# untitled.net
KiCad netlist of a schematic drawn in EAGLE
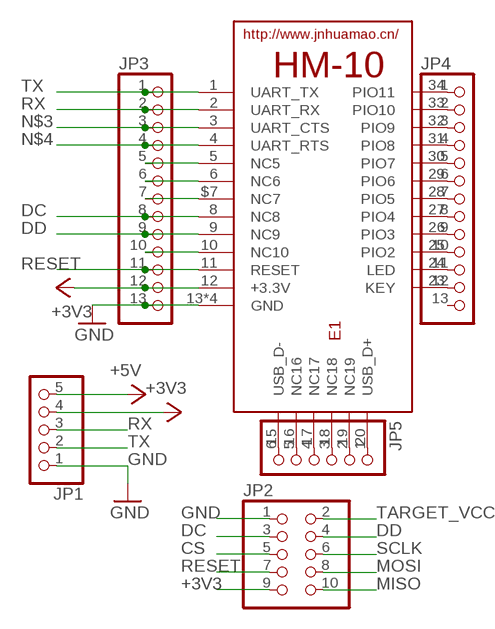
[diagram p0: schematic, sheet 1]

(export (version "E")
  (design (tool "Eeschema 10.0.6"))
  (components
    (comp (ref "E1")
      (value "HM-10-BOARD")
      (footprint "eagle-import:26.9X13X2.2_BOARD")
      (libsource (lib "eagle-import") (part "HM-10-BOARD"))
    )
    (comp (ref "JP1")
      (value "PINHD-1X5")
      (footprint "eagle-import:1X05")
      (libsource (lib "eagle-import") (part "PINHD-1X5"))
    )
    (comp (ref "JP2")
      (value "PINHD-2X5")
      (footprint "eagle-import:2X05")
      (libsource (lib "eagle-import") (part "PINHD-2X5"))
    )
    (comp (ref "JP3")
      (value "PINHD-1X13")
      (footprint "eagle-import:1X13")
      (libsource (lib "eagle-import") (part "PINHD-1X13"))
    )
    (comp (ref "JP4")
      (value "PINHD-1X13")
      (footprint "eagle-import:1X13")
      (libsource (lib "eagle-import") (part "PINHD-1X13"))
    )
    (comp (ref "JP5")
      (value "PINHD-1X6")
      (footprint "eagle-import:1X06")
      (libsource (lib "eagle-import") (part "PINHD-1X6"))
    )
  )
  (nets
    (net (code "1") (name "+3V3") (class "Default")
      (node (ref "E1") (pin "12") (pinfunction "+3.3V_12") (pintype "bidirectional"))
      (node (ref "JP1") (pin "4") (pinfunction "4_4") (pintype "passive"))
      (node (ref "JP2") (pin "9") (pinfunction "9_9") (pintype "passive"))
      (node (ref "JP3") (pin "12") (pinfunction "12_12") (pintype "passive"))
    )
    (net (code "2") (name "+5V") (class "Default")
      (node (ref "JP1") (pin "5") (pinfunction "5_5") (pintype "passive"))
    )
    (net (code "3") (name "/CS") (class "Default")
      (node (ref "JP2") (pin "5") (pinfunction "5_5") (pintype "passive"))
    )
    (net (code "4") (name "/DC") (class "Default")
      (node (ref "E1") (pin "8") (pinfunction "NC8_8") (pintype "bidirectional"))
      (node (ref "JP2") (pin "3") (pinfunction "3_3") (pintype "passive"))
      (node (ref "JP3") (pin "8") (pinfunction "8_8") (pintype "passive"))
    )
    (net (code "5") (name "/DD") (class "Default")
      (node (ref "E1") (pin "9") (pinfunction "NC9_9") (pintype "bidirectional"))
      (node (ref "JP2") (pin "4") (pinfunction "4_4") (pintype "passive"))
      (node (ref "JP3") (pin "9") (pinfunction "9_9") (pintype "passive"))
    )
    (net (code "6") (name "/MISO") (class "Default")
      (node (ref "JP2") (pin "10") (pinfunction "10_10") (pintype "passive"))
    )
    (net (code "7") (name "/MOSI") (class "Default")
      (node (ref "JP2") (pin "8") (pinfunction "8_8") (pintype "passive"))
    )
    (net (code "8") (name "/N$3") (class "Default")
      (node (ref "E1") (pin "3") (pinfunction "UART_CTS_3") (pintype "bidirectional"))
      (node (ref "JP3") (pin "3") (pinfunction "3_3") (pintype "passive"))
    )
    (net (code "9") (name "/N$4") (class "Default")
      (node (ref "E1") (pin "4") (pinfunction "UART_RTS_4") (pintype "bidirectional"))
      (node (ref "JP3") (pin "4") (pinfunction "4_4") (pintype "passive"))
    )
    (net (code "10") (name "/RESET") (class "Default")
      (node (ref "E1") (pin "11") (pinfunction "RESET_11") (pintype "bidirectional"))
      (node (ref "JP2") (pin "7") (pinfunction "7_7") (pintype "passive"))
      (node (ref "JP3") (pin "11") (pinfunction "11_11") (pintype "passive"))
    )
    (net (code "11") (name "/RX") (class "Default")
      (node (ref "E1") (pin "2") (pinfunction "UART_RX_2") (pintype "bidirectional"))
      (node (ref "JP1") (pin "3") (pinfunction "3_3") (pintype "passive"))
      (node (ref "JP3") (pin "2") (pinfunction "2_2") (pintype "passive"))
    )
    (net (code "12") (name "/SCLK") (class "Default")
      (node (ref "JP2") (pin "6") (pinfunction "6_6") (pintype "passive"))
    )
    (net (code "13") (name "/TARGET_VCC") (class "Default")
      (node (ref "JP2") (pin "2") (pinfunction "2_2") (pintype "passive"))
    )
    (net (code "14") (name "/TX") (class "Default")
      (node (ref "E1") (pin "1") (pinfunction "UART_TX_1") (pintype "bidirectional"))
      (node (ref "JP1") (pin "2") (pinfunction "2_2") (pintype "passive"))
      (node (ref "JP3") (pin "1") (pinfunction "1_1") (pintype "passive"))
    )
    (net (code "15") (name "GND") (class "Default")
      (node (ref "E1") (pin "13") (pinfunction "GND_13") (pintype "bidirectional"))
      (node (ref "E1") (pin "14") (pinfunction "GND_14") (pintype "bidirectional"))
      (node (ref "E1") (pin "21") (pinfunction "GND_21") (pintype "bidirectional"))
      (node (ref "E1") (pin "22") (pinfunction "GND_22") (pintype "bidirectional"))
      (node (ref "JP1") (pin "1") (pinfunction "1_1") (pintype "passive"))
      (node (ref "JP2") (pin "1") (pinfunction "1_1") (pintype "passive"))
      (node (ref "JP3") (pin "13") (pinfunction "13_13") (pintype "passive"))
    )
    (net (code "16") (name "Net-(E1-KEY)") (class "Default")
      (node (ref "E1") (pin "23") (pinfunction "KEY_23") (pintype "bidirectional"))
      (node (ref "JP4") (pin "12") (pinfunction "12_12") (pintype "passive"))
    )
    (net (code "17") (name "Net-(E1-LED)") (class "Default")
      (node (ref "E1") (pin "24") (pinfunction "LED_24") (pintype "bidirectional"))
      (node (ref "JP4") (pin "11") (pinfunction "11_11") (pintype "passive"))
    )
    (net (code "18") (name "Net-(E1-NC5)") (class "Default")
      (node (ref "E1") (pin "5") (pinfunction "NC5_5") (pintype "bidirectional"))
      (node (ref "JP3") (pin "5") (pinfunction "5_5") (pintype "passive"))
    )
    (net (code "19") (name "Net-(E1-NC6)") (class "Default")
      (node (ref "E1") (pin "6") (pinfunction "NC6_6") (pintype "bidirectional"))
      (node (ref "JP3") (pin "6") (pinfunction "6_6") (pintype "passive"))
    )
    (net (code "20") (name "Net-(E1-NC7)") (class "Default")
      (node (ref "E1") (pin "$7") (pinfunction "NC7_$7") (pintype "bidirectional"))
      (node (ref "JP3") (pin "7") (pinfunction "7_7") (pintype "passive"))
    )
    (net (code "21") (name "Net-(E1-NC10)") (class "Default")
      (node (ref "E1") (pin "10") (pinfunction "NC10_10") (pintype "bidirectional"))
      (node (ref "JP3") (pin "10") (pinfunction "10_10") (pintype "passive"))
    )
    (net (code "22") (name "Net-(E1-NC16)") (class "Default")
      (node (ref "E1") (pin "16") (pinfunction "NC16_16") (pintype "bidirectional"))
      (node (ref "JP5") (pin "5") (pinfunction "5_5") (pintype "passive"))
    )
    (net (code "23") (name "Net-(E1-NC17)") (class "Default")
      (node (ref "E1") (pin "17") (pinfunction "NC17_17") (pintype "bidirectional"))
      (node (ref "JP5") (pin "4") (pinfunction "4_4") (pintype "passive"))
    )
    (net (code "24") (name "Net-(E1-NC18)") (class "Default")
      (node (ref "E1") (pin "18") (pinfunction "NC18_18") (pintype "bidirectional"))
      (node (ref "JP5") (pin "3") (pinfunction "3_3") (pintype "passive"))
    )
    (net (code "25") (name "Net-(E1-NC19)") (class "Default")
      (node (ref "E1") (pin "19") (pinfunction "NC19_19") (pintype "bidirectional"))
      (node (ref "JP5") (pin "2") (pinfunction "2_2") (pintype "passive"))
    )
    (net (code "26") (name "Net-(E1-PIO2)") (class "Default")
      (node (ref "E1") (pin "25") (pinfunction "PIO2_25") (pintype "bidirectional"))
      (node (ref "JP4") (pin "10") (pinfunction "10_10") (pintype "passive"))
    )
    (net (code "27") (name "Net-(E1-PIO3)") (class "Default")
      (node (ref "E1") (pin "26") (pinfunction "PIO3_26") (pintype "bidirectional"))
      (node (ref "JP4") (pin "9") (pinfunction "9_9") (pintype "passive"))
    )
    (net (code "28") (name "Net-(E1-PIO4)") (class "Default")
      (node (ref "E1") (pin "27") (pinfunction "PIO4_27") (pintype "bidirectional"))
      (node (ref "JP4") (pin "8") (pinfunction "8_8") (pintype "passive"))
    )
    (net (code "29") (name "Net-(E1-PIO5)") (class "Default")
      (node (ref "E1") (pin "28") (pinfunction "PIO5_28") (pintype "bidirectional"))
      (node (ref "JP4") (pin "7") (pinfunction "7_7") (pintype "passive"))
    )
    (net (code "30") (name "Net-(E1-PIO6)") (class "Default")
      (node (ref "E1") (pin "29") (pinfunction "PIO6_29") (pintype "bidirectional"))
      (node (ref "JP4") (pin "6") (pinfunction "6_6") (pintype "passive"))
    )
    (net (code "31") (name "Net-(E1-PIO7)") (class "Default")
      (node (ref "E1") (pin "30") (pinfunction "PIO7_30") (pintype "bidirectional"))
      (node (ref "JP4") (pin "5") (pinfunction "5_5") (pintype "passive"))
    )
    (net (code "32") (name "Net-(E1-PIO8)") (class "Default")
      (node (ref "E1") (pin "31") (pinfunction "PIO8_31") (pintype "bidirectional"))
      (node (ref "JP4") (pin "4") (pinfunction "4_4") (pintype "passive"))
    )
    (net (code "33") (name "Net-(E1-PIO9)") (class "Default")
      (node (ref "E1") (pin "32") (pinfunction "PIO9_32") (pintype "bidirectional"))
      (node (ref "JP4") (pin "3") (pinfunction "3_3") (pintype "passive"))
    )
    (net (code "34") (name "Net-(E1-PIO10)") (class "Default")
      (node (ref "E1") (pin "33") (pinfunction "PIO10_33") (pintype "bidirectional"))
      (node (ref "JP4") (pin "2") (pinfunction "2_2") (pintype "passive"))
    )
    (net (code "35") (name "Net-(E1-PIO11)") (class "Default")
      (node (ref "E1") (pin "34") (pinfunction "PIO11_34") (pintype "bidirectional"))
      (node (ref "JP4") (pin "1") (pinfunction "1_1") (pintype "passive"))
    )
    (net (code "36") (name "Net-(E1-USB_D+)") (class "Default")
      (node (ref "E1") (pin "20") (pinfunction "USB_D+_20") (pintype "bidirectional"))
      (node (ref "JP5") (pin "1") (pinfunction "1_1") (pintype "passive"))
    )
    (net (code "37") (name "Net-(E1-USB_D-)") (class "Default")
      (node (ref "E1") (pin "15") (pinfunction "USB_D-_15") (pintype "bidirectional"))
      (node (ref "JP5") (pin "6") (pinfunction "6_6") (pintype "passive"))
    )
    (net (code "38") (name "unconnected-(JP4-Pad13)") (class "Default")
      (node (ref "JP4") (pin "13") (pinfunction "13_13") (pintype "passive"))
    )
  )
)
